# 02_buck_converter.net
KiCad netlist of a schematic drawn in Altium Designer
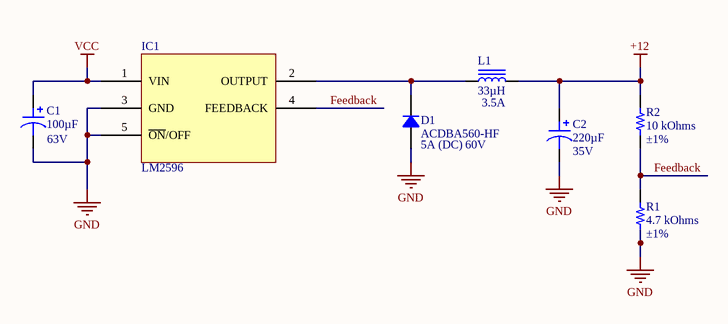
[diagram p0: 02_buck_converter.SchDoc]

(export (version "E")
  (design (tool "Eeschema 10.0.6"))
  (components
    (comp (ref "C1")
      (value "100µF")
      (footprint "CAP TH ALUM ELEC D8.00mm S3.50mm H12.50mm")
      (description "CAP ALUM 100UF 20% 63V RADIAL")
      (fields
        (field (name "PART NUMBER") "ECA-1JM101")
        (field (name "MANUFACTURER") "Panasonic Electronic Components")
        (field (name "VOLTAGE - RATED") "63V")
      )
      (libsource (lib "Celestial Altium Library - altium_library") (part "Polarised Capacitor"))
    )
    (comp (ref "C2")
      (value "220µF")
      (footprint "CAP TH ALUM ELEC D8.00mm S3.50mm H12.50mm")
      (description "CAP ALUM 220UF 20% 35V RADIAL")
      (fields
        (field (name "PART NUMBER") "ECA-1VM221")
        (field (name "MANUFACTURER") "Panasonic Electronic Components")
        (field (name "VOLTAGE - RATED") "35V")
      )
      (libsource (lib "Celestial Altium Library - altium_library") (part "Polarised Capacitor"))
    )
    (comp (ref "D1")
      (value "ACDBA560-HF")
      (footprint "DO214AC SMA")
      (description "DIODE SCHOTTKY 60V 5A DO214AC")
      (fields
        (field (name "CURRENT - AVERAGE RECTIFIED (IO)") "5A (DC)")
        (field (name "MANUFACTURER") "Comchip Technology")
        (field (name "VOLTAGE - DC REVERSE (VR) (MAX)") "60V")
      )
      (libsource (lib "Celestial Altium Library - altium_library") (part "Diode"))
    )
    (comp (ref "IC1") (value "LM2596") (footprint "D2PAK") (libsource (lib "Kutuphane") (part "LM2596")))
    (comp (ref "L1")
      (value "33µH")
      (footprint "BOURNS SRR1280")
      (description "FIXED IND 33UH 3.5A 57 MOHM SMD")
      (fields
        (field (name "PART NUMBER") "SRR1280-330M")
        (field (name "CURRENT RATING (AMPS)") "3.5A")
        (field (name "MANUFACTURER") "Bourns Inc.")
      )
      (libsource (lib "Celestial Altium Library - altium_library") (part "Inductor"))
    )
    (comp (ref "R1")
      (value "4.7 kOhms")
      (footprint "RES 0805_2012")
      (description "RES SMD 4.7K OHM 1% 1/8W 0805")
      (fields
        (field (name "PART NUMBER") "RC0805FR-074K7P")
        (field (name "MANUFACTURER") "Yageo")
        (field (name "TOLERANCE") "±1%")
      )
      (libsource (lib "Celestial Altium Library - altium_library") (part "Resistor"))
    )
    (comp (ref "R2")
      (value "10 kOhms")
      (footprint "RES 0805_2012")
      (description "RES 10K OHM 1% 1/4W 0805")
      (fields
        (field (name "PART NUMBER") "RNCP0805FTD10K0")
        (field (name "MANUFACTURER") "Stackpole Electronics Inc")
        (field (name "TOLERANCE") "±1%")
      )
      (libsource (lib "Celestial Altium Library - altium_library") (part "Resistor"))
    )
  )
  (nets
    (net (code "1") (name "+12") (class "Default")
      (node (ref "C2") (pin "1") (pinfunction "1_1") (pintype "passive"))
      (node (ref "L1") (pin "2") (pinfunction "2_2") (pintype "passive"))
      (node (ref "R2") (pin "2") (pinfunction "2_2") (pintype "passive"))
    )
    (net (code "2") (name "/Feedback") (class "Default")
      (node (ref "IC1") (pin "4") (pinfunction "FEEDBACK_4") (pintype "passive"))
      (node (ref "R1") (pin "2") (pinfunction "2_2") (pintype "passive"))
      (node (ref "R2") (pin "1") (pinfunction "1_1") (pintype "passive"))
    )
    (net (code "3") (name "GND") (class "Default")
      (node (ref "C1") (pin "2") (pinfunction "2_2") (pintype "passive"))
      (node (ref "C2") (pin "2") (pinfunction "2_2") (pintype "passive"))
      (node (ref "D1") (pin "1") (pinfunction "1_1") (pintype "passive"))
      (node (ref "IC1") (pin "3") (pinfunction "GND_3") (pintype "passive"))
      (node (ref "IC1") (pin "5") (pinfunction "~{ON}/OFF_5") (pintype "passive"))
      (node (ref "R1") (pin "1") (pinfunction "1_1") (pintype "passive"))
    )
    (net (code "4") (name "Net-(IC1-OUTPUT)") (class "Default")
      (node (ref "D1") (pin "2") (pinfunction "2_2") (pintype "passive"))
      (node (ref "IC1") (pin "2") (pinfunction "OUTPUT_2") (pintype "passive"))
      (node (ref "L1") (pin "1") (pinfunction "1_1") (pintype "passive"))
    )
    (net (code "5") (name "VCC") (class "Default")
      (node (ref "C1") (pin "1") (pinfunction "1_1") (pintype "passive"))
      (node (ref "IC1") (pin "1") (pinfunction "VIN_1") (pintype "passive"))
    )
  )
)
